# lm317.net
KiCad netlist of a schematic drawn in EAGLE
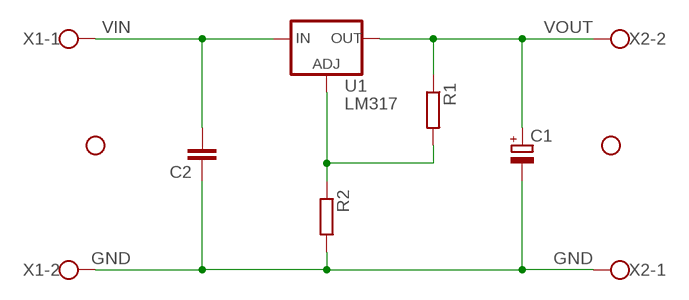
[diagram p0: schematic, sheet 1]

(export (version "E")
  (design (tool "Eeschema 10.0.6"))
  (components
    (comp (ref "C1")
      (value "CPOL-EUE2.5-6")
      (footprint "eagle-import:E2,5-6")
      (libsource (lib "eagle-import") (part "CPOL-EUE2.5-6"))
    )
    (comp (ref "C2")
      (value "C-EUC1206K")
      (footprint "eagle-import:C1206K")
      (libsource (lib "eagle-import") (part "C-EUC1206K"))
    )
    (comp (ref "R1")
      (value "R-EU_M1206")
      (footprint "eagle-import:M1206")
      (libsource (lib "eagle-import") (part "R-EU_M1206"))
    )
    (comp (ref "R2")
      (value "R-EU_M1206")
      (footprint "eagle-import:M1206")
      (libsource (lib "eagle-import") (part "R-EU_M1206"))
    )
    (comp (ref "STANDOFF1")
      (value "STAND-OFF")
      (footprint "eagle-import:STAND-OFF")
      (libsource (lib "eagle-import") (part "STAND-OFF"))
    )
    (comp (ref "STANDOFF2")
      (value "STAND-OFF")
      (footprint "eagle-import:STAND-OFF")
      (libsource (lib "eagle-import") (part "STAND-OFF"))
    )
    (comp (ref "U1")
      (value "LM317")
      (footprint "eagle-import:TO220-ADJ")
      (libsource (lib "eagle-import") (part "V_REG_317SINK"))
    )
    (comp (ref "X1")
      (value "W237-102")
      (footprint "eagle-import:W237-102")
      (fields (field (name "MPN") "237-102"))
      (libsource (lib "eagle-import") (part "W237-102"))
    )
    (comp (ref "X2")
      (value "W237-102")
      (footprint "eagle-import:W237-102")
      (fields (field (name "MPN") "237-102"))
      (libsource (lib "eagle-import") (part "W237-102"))
    )
  )
  (nets
    (net (code "1") (name "/GND") (class "Default")
      (node (ref "C1") (pin "-") (pinfunction "-_-") (pintype "passive"))
      (node (ref "C2") (pin "1") (pinfunction "1_1") (pintype "passive"))
      (node (ref "R2") (pin "2") (pinfunction "2_2") (pintype "passive"))
      (node (ref "X1") (pin "2") (pinfunction "KL_2") (pintype "passive"))
      (node (ref "X2") (pin "1") (pinfunction "KL_1") (pintype "passive"))
    )
    (net (code "2") (name "/VIN") (class "Default")
      (node (ref "C2") (pin "2") (pinfunction "2_2") (pintype "passive"))
      (node (ref "U1") (pin "IN") (pinfunction "IN_IN") (pintype "input"))
      (node (ref "X1") (pin "1") (pinfunction "KL_1") (pintype "passive"))
    )
    (net (code "3") (name "/VOUT") (class "Default")
      (node (ref "C1") (pin "+") (pinfunction "+_+") (pintype "passive"))
      (node (ref "R1") (pin "1") (pinfunction "1_1") (pintype "passive"))
      (node (ref "U1") (pin "OUT") (pinfunction "OUT_OUT") (pintype "output"))
      (node (ref "X2") (pin "2") (pinfunction "KL_2") (pintype "passive"))
    )
    (net (code "4") (name "Net-(R1-Pad2)") (class "Default")
      (node (ref "R1") (pin "2") (pinfunction "2_2") (pintype "passive"))
      (node (ref "R2") (pin "1") (pinfunction "1_1") (pintype "passive"))
      (node (ref "U1") (pin "ADJ") (pinfunction "ADJ_ADJ") (pintype "input"))
    )
  )
)
